# User_Interface.net
KiCad netlist of a schematic drawn in Altium Designer
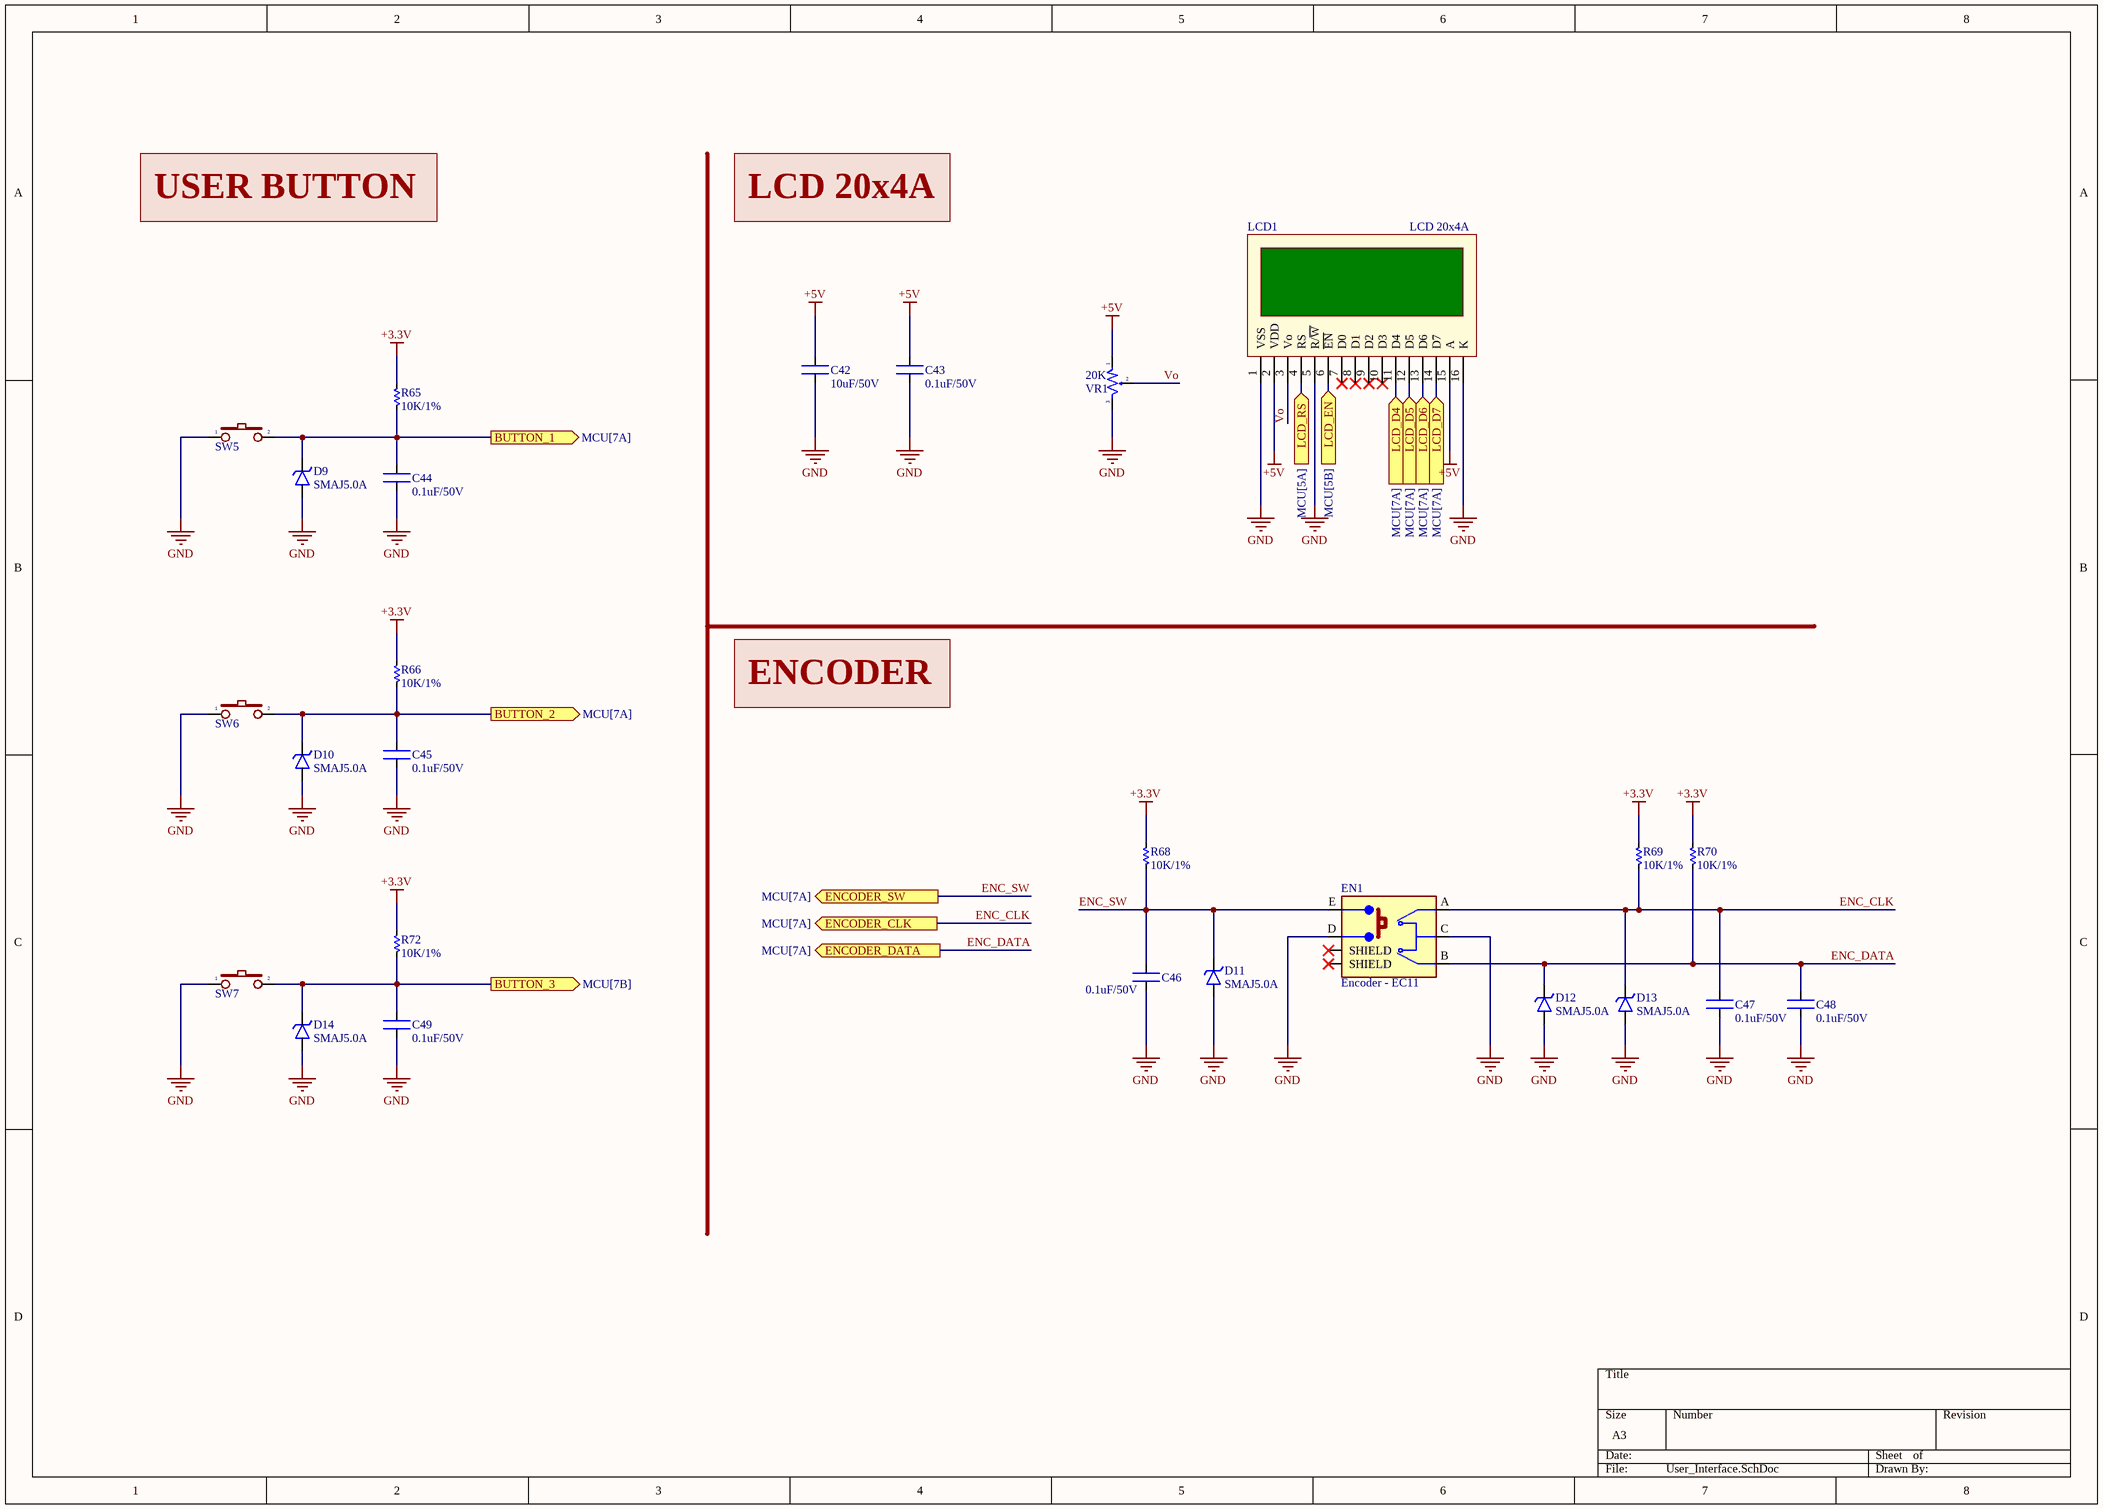
[diagram p0: User_Interface.SchDoc]

(export (version "E")
  (design (tool "Eeschema 10.0.6"))
  (components
    (comp (ref "C42")
      (value "10uF/50V")
      (footprint "CAP - 0603")
      (description "CAPACITOR SMD - KEMET")
      (libsource (lib "NewLibrary") (part "CAPACITOR"))
    )
    (comp (ref "C43")
      (value "0.1uF/50V")
      (footprint "CAP - 0603")
      (description "CAPACITOR SMD - KEMET")
      (libsource (lib "NewLibrary") (part "CAPACITOR"))
    )
    (comp (ref "C44")
      (value "0.1uF/50V")
      (footprint "CAP - 0603")
      (description "CAPACITOR SMD - KEMET")
      (libsource (lib "NewLibrary") (part "CAPACITOR"))
    )
    (comp (ref "C45")
      (value "0.1uF/50V")
      (footprint "CAP - 0603")
      (description "CAPACITOR SMD - KEMET")
      (libsource (lib "NewLibrary") (part "CAPACITOR"))
    )
    (comp (ref "C46")
      (value "0.1uF/50V")
      (footprint "CAP - 0603")
      (description "CAPACITOR SMD - KEMET")
      (libsource (lib "NewLibrary") (part "CAPACITOR"))
    )
    (comp (ref "C47")
      (value "0.1uF/50V")
      (footprint "CAP - 0603")
      (description "CAPACITOR SMD - KEMET")
      (libsource (lib "NewLibrary") (part "CAPACITOR"))
    )
    (comp (ref "C48")
      (value "0.1uF/50V")
      (footprint "CAP - 0603")
      (description "CAPACITOR SMD - KEMET")
      (libsource (lib "NewLibrary") (part "CAPACITOR"))
    )
    (comp (ref "C49")
      (value "0.1uF/50V")
      (footprint "CAP - 0603")
      (description "CAPACITOR SMD - KEMET")
      (libsource (lib "NewLibrary") (part "CAPACITOR"))
    )
    (comp (ref "D9")
      (value "SMAJ5.0A")
      (footprint "DO-214AC")
      (description "TVS, 400W, 5V, Unidirectional")
      (libsource (lib "NewLibrary") (part "SMAJ5.0A"))
    )
    (comp (ref "D10")
      (value "SMAJ5.0A")
      (footprint "DO-214AC")
      (description "TVS, 400W, 5V, Unidirectional")
      (libsource (lib "NewLibrary") (part "SMAJ5.0A"))
    )
    (comp (ref "D11")
      (value "SMAJ5.0A")
      (footprint "DO-214AC")
      (description "TVS, 400W, 5V, Unidirectional")
      (libsource (lib "NewLibrary") (part "SMAJ5.0A"))
    )
    (comp (ref "D12")
      (value "SMAJ5.0A")
      (footprint "DO-214AC")
      (description "TVS, 400W, 5V, Unidirectional")
      (libsource (lib "NewLibrary") (part "SMAJ5.0A"))
    )
    (comp (ref "D13")
      (value "SMAJ5.0A")
      (footprint "DO-214AC")
      (description "TVS, 400W, 5V, Unidirectional")
      (libsource (lib "NewLibrary") (part "SMAJ5.0A"))
    )
    (comp (ref "D14")
      (value "SMAJ5.0A")
      (footprint "DO-214AC")
      (description "TVS, 400W, 5V, Unidirectional")
      (libsource (lib "NewLibrary") (part "SMAJ5.0A"))
    )
    (comp (ref "EN1")
      (value "Encoder - EC11")
      (footprint "Encoder - EC11")
      (description "Bourns PEC11R-4015F-S0024")
      (libsource (lib "NewLibrary") (part "Encoder - EC11"))
    )
    (comp (ref "LCD1")
      (value "LCD 20x4A")
      (footprint "LCD-20x4A-4-Holes")
      (description "LCD 2004")
      (libsource (lib "NewLibrary") (part "LCD 20x4A"))
    )
    (comp (ref "R65")
      (value "10K/1%")
      (footprint "RES - 0603")
      (description "Resistor SMD - YAGEO")
      (libsource (lib "NewLibrary") (part "RESISTOR"))
    )
    (comp (ref "R66")
      (value "10K/1%")
      (footprint "RES - 0603")
      (description "Resistor SMD - YAGEO")
      (libsource (lib "NewLibrary") (part "RESISTOR"))
    )
    (comp (ref "R68")
      (value "10K/1%")
      (footprint "RES - 0603")
      (description "Resistor SMD - YAGEO")
      (libsource (lib "NewLibrary") (part "RESISTOR"))
    )
    (comp (ref "R69")
      (value "10K/1%")
      (footprint "RES - 0603")
      (description "Resistor SMD - YAGEO")
      (libsource (lib "NewLibrary") (part "RESISTOR"))
    )
    (comp (ref "R70")
      (value "10K/1%")
      (footprint "RES - 0603")
      (description "Resistor SMD - YAGEO")
      (libsource (lib "NewLibrary") (part "RESISTOR"))
    )
    (comp (ref "R72")
      (value "10K/1%")
      (footprint "RES - 0603")
      (description "Resistor SMD - YAGEO")
      (libsource (lib "NewLibrary") (part "RESISTOR"))
    )
    (comp (ref "SW5")
      (value "Button 4 Pins")
      (footprint "SW-SMD-6x6mm")
      (description "DIP Button 4 Pins")
      (libsource (lib "NewLibrary") (part "Button 4 Pins"))
    )
    (comp (ref "SW6")
      (value "Button 4 Pins")
      (footprint "SW-SMD-6x6mm")
      (description "DIP Button 4 Pins")
      (libsource (lib "NewLibrary") (part "Button 4 Pins"))
    )
    (comp (ref "SW7")
      (value "Button 4 Pins")
      (footprint "SW-SMD-6x6mm")
      (description "DIP Button 4 Pins")
      (libsource (lib "NewLibrary") (part "Button 4 Pins"))
    )
    (comp (ref "VR1")
      (value "20K")
      (footprint "VR 3x3")
      (description "VR")
      (libsource (lib "NewLibrary") (part "VARIABLE RESISTOR"))
    )
  )
  (nets
    (net (code "1") (name "+3.3V") (class "Default")
      (node (ref "R65") (pin "2") (pinfunction "2_2") (pintype "passive"))
      (node (ref "R66") (pin "2") (pinfunction "2_2") (pintype "passive"))
      (node (ref "R68") (pin "2") (pinfunction "2_2") (pintype "passive"))
      (node (ref "R69") (pin "2") (pinfunction "2_2") (pintype "passive"))
      (node (ref "R70") (pin "2") (pinfunction "2_2") (pintype "passive"))
      (node (ref "R72") (pin "1") (pinfunction "1_1") (pintype "passive"))
    )
    (net (code "2") (name "+5V") (class "Default")
      (node (ref "C42") (pin "2") (pinfunction "2_2") (pintype "passive"))
      (node (ref "C43") (pin "2") (pinfunction "2_2") (pintype "passive"))
      (node (ref "LCD1") (pin "15") (pinfunction "A_15") (pintype "passive"))
      (node (ref "LCD1") (pin "2") (pinfunction "VDD_2") (pintype "passive"))
      (node (ref "VR1") (pin "1") (pinfunction "1_1") (pintype "passive"))
    )
    (net (code "3") (name "/BUTTON_1") (class "Default")
      (node (ref "C44") (pin "2") (pinfunction "2_2") (pintype "passive"))
      (node (ref "D9") (pin "C") (pinfunction "1_C") (pintype "passive"))
      (node (ref "R65") (pin "1") (pinfunction "1_1") (pintype "passive"))
      (node (ref "SW5") (pin "2") (pinfunction "2_2") (pintype "passive"))
    )
    (net (code "4") (name "/BUTTON_2") (class "Default")
      (node (ref "C45") (pin "2") (pinfunction "2_2") (pintype "passive"))
      (node (ref "D10") (pin "C") (pinfunction "1_C") (pintype "passive"))
      (node (ref "R66") (pin "1") (pinfunction "1_1") (pintype "passive"))
      (node (ref "SW6") (pin "2") (pinfunction "2_2") (pintype "passive"))
    )
    (net (code "5") (name "/BUTTON_3") (class "Default")
      (node (ref "C49") (pin "2") (pinfunction "2_2") (pintype "passive"))
      (node (ref "D14") (pin "C") (pinfunction "1_C") (pintype "passive"))
      (node (ref "R72") (pin "2") (pinfunction "2_2") (pintype "passive"))
      (node (ref "SW7") (pin "2") (pinfunction "2_2") (pintype "passive"))
    )
    (net (code "6") (name "/ENC_CLK") (class "Default")
      (node (ref "C47") (pin "2") (pinfunction "2_2") (pintype "passive"))
      (node (ref "D13") (pin "C") (pinfunction "1_C") (pintype "passive"))
      (node (ref "EN1") (pin "A") (pinfunction "A_A") (pintype "passive"))
      (node (ref "R69") (pin "1") (pinfunction "1_1") (pintype "passive"))
    )
    (net (code "7") (name "/ENC_DATA") (class "Default")
      (node (ref "C48") (pin "2") (pinfunction "2_2") (pintype "passive"))
      (node (ref "D12") (pin "C") (pinfunction "1_C") (pintype "passive"))
      (node (ref "EN1") (pin "B") (pinfunction "B_B") (pintype "passive"))
      (node (ref "R70") (pin "1") (pinfunction "1_1") (pintype "passive"))
    )
    (net (code "8") (name "/ENC_SW") (class "Default")
      (node (ref "C46") (pin "2") (pinfunction "2_2") (pintype "passive"))
      (node (ref "D11") (pin "C") (pinfunction "1_C") (pintype "passive"))
      (node (ref "EN1") (pin "E") (pinfunction "S2_E") (pintype "passive"))
      (node (ref "R68") (pin "1") (pinfunction "1_1") (pintype "passive"))
    )
    (net (code "9") (name "/LCD_D4") (class "Default")
      (node (ref "LCD1") (pin "11") (pinfunction "D4_11") (pintype "passive"))
    )
    (net (code "10") (name "/LCD_D5") (class "Default")
      (node (ref "LCD1") (pin "12") (pinfunction "D5_12") (pintype "passive"))
    )
    (net (code "11") (name "/LCD_D6") (class "Default")
      (node (ref "LCD1") (pin "13") (pinfunction "D6_13") (pintype "passive"))
    )
    (net (code "12") (name "/LCD_D7") (class "Default")
      (node (ref "LCD1") (pin "14") (pinfunction "D7_14") (pintype "passive"))
    )
    (net (code "13") (name "/LCD_EN") (class "Default")
      (node (ref "LCD1") (pin "6") (pinfunction "~{EN}_6") (pintype "passive"))
    )
    (net (code "14") (name "/LCD_RS") (class "Default")
      (node (ref "LCD1") (pin "4") (pinfunction "RS_4") (pintype "passive"))
    )
    (net (code "15") (name "/Vo") (class "Default")
      (node (ref "LCD1") (pin "3") (pinfunction "Vo_3") (pintype "passive"))
      (node (ref "VR1") (pin "2") (pinfunction "2_2") (pintype "passive"))
    )
    (net (code "16") (name "GND") (class "Default")
      (node (ref "C42") (pin "1") (pinfunction "1_1") (pintype "passive"))
      (node (ref "C43") (pin "1") (pinfunction "1_1") (pintype "passive"))
      (node (ref "C44") (pin "1") (pinfunction "1_1") (pintype "passive"))
      (node (ref "C45") (pin "1") (pinfunction "1_1") (pintype "passive"))
      (node (ref "C46") (pin "1") (pinfunction "1_1") (pintype "passive"))
      (node (ref "C47") (pin "1") (pinfunction "1_1") (pintype "passive"))
      (node (ref "C48") (pin "1") (pinfunction "1_1") (pintype "passive"))
      (node (ref "C49") (pin "1") (pinfunction "1_1") (pintype "passive"))
      (node (ref "D10") (pin "A") (pinfunction "A_A") (pintype "passive"))
      (node (ref "D11") (pin "A") (pinfunction "A_A") (pintype "passive"))
      (node (ref "D12") (pin "A") (pinfunction "A_A") (pintype "passive"))
      (node (ref "D13") (pin "A") (pinfunction "A_A") (pintype "passive"))
      (node (ref "D14") (pin "A") (pinfunction "A_A") (pintype "passive"))
      (node (ref "D9") (pin "A") (pinfunction "A_A") (pintype "passive"))
      (node (ref "EN1") (pin "C") (pinfunction "C_C") (pintype "passive"))
      (node (ref "EN1") (pin "D") (pinfunction "S1_D") (pintype "passive"))
      (node (ref "LCD1") (pin "1") (pinfunction "VSS_1") (pintype "passive"))
      (node (ref "LCD1") (pin "16") (pinfunction "K_16") (pintype "passive"))
      (node (ref "LCD1") (pin "5") (pinfunction "R/~{W}_5") (pintype "passive"))
      (node (ref "SW5") (pin "1") (pinfunction "1_1") (pintype "passive"))
      (node (ref "SW6") (pin "1") (pinfunction "1_1") (pintype "passive"))
      (node (ref "SW7") (pin "1") (pinfunction "1_1") (pintype "passive"))
      (node (ref "VR1") (pin "3") (pinfunction "3_3") (pintype "passive"))
    )
    (net (code "17") (name "unconnected-(EN1-SHIELD-PadSH1)") (class "Default")
      (node (ref "EN1") (pin "SH1") (pinfunction "SHIELD_SH1") (pintype "passive+no_connect"))
    )
    (net (code "18") (name "unconnected-(EN1-SHIELD-PadSH2)") (class "Default")
      (node (ref "EN1") (pin "SH2") (pinfunction "SHIELD_SH2") (pintype "passive+no_connect"))
    )
    (net (code "19") (name "unconnected-(LCD1-D0-Pad7)") (class "Default")
      (node (ref "LCD1") (pin "7") (pinfunction "D0_7") (pintype "passive+no_connect"))
    )
    (net (code "20") (name "unconnected-(LCD1-D1-Pad8)") (class "Default")
      (node (ref "LCD1") (pin "8") (pinfunction "D1_8") (pintype "passive+no_connect"))
    )
    (net (code "21") (name "unconnected-(LCD1-D2-Pad9)") (class "Default")
      (node (ref "LCD1") (pin "9") (pinfunction "D2_9") (pintype "passive+no_connect"))
    )
    (net (code "22") (name "unconnected-(LCD1-D3-Pad10)") (class "Default")
      (node (ref "LCD1") (pin "10") (pinfunction "D3_10") (pintype "passive+no_connect"))
    )
  )
)
